# PROC091F_BT_DISPLAY.net
KiCad netlist of a schematic drawn in Altium Designer
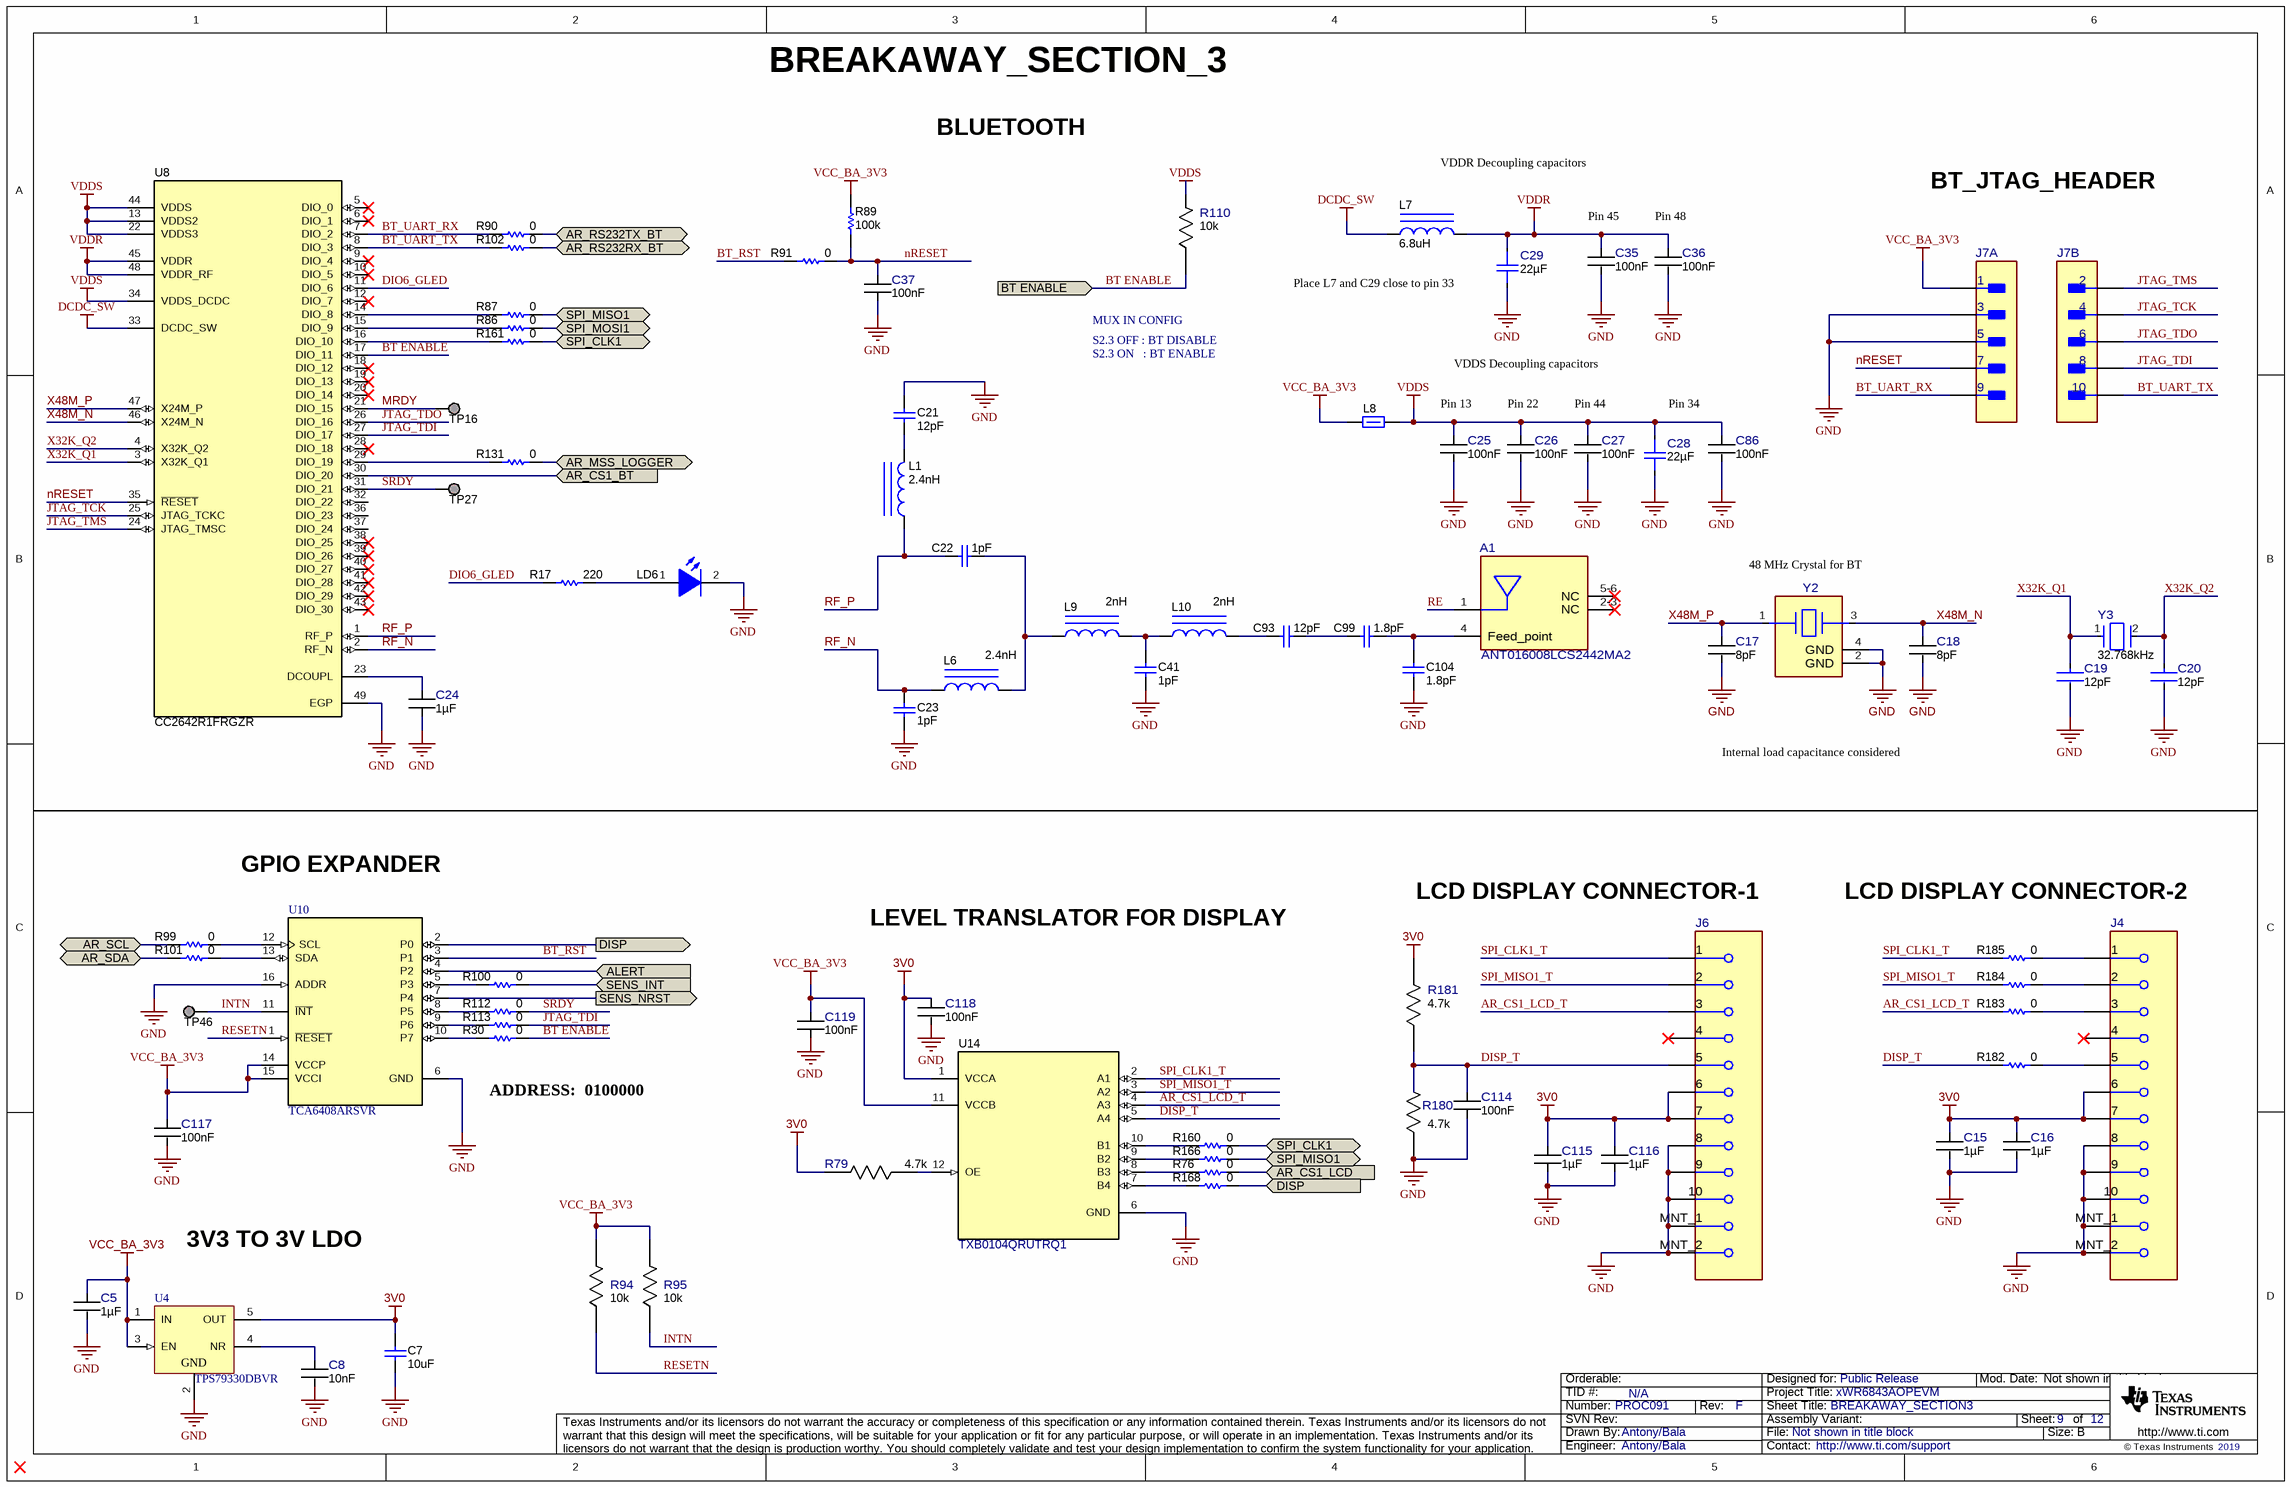
[diagram p0: PROC091F_BT_DISPLAY.SchDoc]

(export (version "E")
  (design (tool "Eeschema 10.0.6"))
  (components
    (comp (ref "A1")
      (value "ANT016008LCS2442MA2")
      (footprint "FP-ANT016008LCS2442MA2_SMT_ANT-0")
      (description "RF ANT 2.4GHZ CHIP SOLDER SMD")
      (fields (field (name "MANUFACTURER") "TDK Corporation"))
      (libsource (lib "Altium Vault - TI") (part "SYM-ANT016008LCS2442MA2"))
    )
    (comp (ref "C5")
      (value "CL03A105MO3NRNH")
      (footprint "FP-CL03A105MO3NRNH_0201-IPC_C")
      (description "1µF ±20% 16V Ceramic Capacitor X5R 0201")
      (fields (field (name "CAP_F") "1µF") (field (name "MANUFACTURER") "Samsung Electro-Mechanics"))
      (libsource (lib "Altium Vault - TI") (part "SYM-B32642B0223J"))
    )
    (comp (ref "C7")
      (value "10uF")
      (footprint "0402_070")
      (description "CAP, CERM, 10 uF, 10 V, +/- 20%, X5R, 0402")
      (fields
        (field (name "MANUFACTURER") "Samsung Electro-Mechanics")
        (field (name "PARTNUMBER") "CL05A106MP5NUNC")
      )
      (libsource (lib "Altium Vault - TI") (part "Capacitor"))
    )
    (comp (ref "C8")
      (value "CL03A103KA3NNNC")
      (footprint "FP-CL03A103KA3NNNC_0201-IPC_C")
      (description "CAP CER 10000PF 25V X5R 0201")
      (fields
        (field (name "CAP_F") "10nF")
        (field (name "MANUFACTURER") "Samsung Electro-Mechanics America, Inc")
      )
      (libsource (lib "Altium Vault - TI") (part "SYM-B32642B0223J"))
    )
    (comp (ref "C15")
      (value "CL03A105MO3NRNH")
      (footprint "FP-CL03A105MO3NRNH_0201-IPC_C")
      (description "1µF ±20% 16V Ceramic Capacitor X5R 0201")
      (fields (field (name "CAP_F") "1µF") (field (name "MANUFACTURER") "Samsung Electro-Mechanics"))
      (libsource (lib "Altium Vault - TI") (part "SYM-B32642B0223J"))
    )
    (comp (ref "C16")
      (value "CL03A105MO3NRNH")
      (footprint "FP-CL03A105MO3NRNH_0201-IPC_C")
      (description "1µF ±20% 16V Ceramic Capacitor X5R 0201")
      (fields (field (name "CAP_F") "1µF") (field (name "MANUFACTURER") "Samsung Electro-Mechanics"))
      (libsource (lib "Altium Vault - TI") (part "SYM-B32642B0223J"))
    )
    (comp (ref "C17")
      (value "GRM0335C1H8R0BA01D")
      (footprint "FP-GRM0335C1H8R0BA01D_0201 (0603 metric)-IPC_C")
      (description "Cap Ceramic 8pF 50V C0G 0.1pF SMD 0201 125°C Paper T/R")
      (fields (field (name "CAP_F") "8pF") (field (name "MANUFACTURER") "Murata"))
      (libsource (lib "Altium Vault - TI") (part "SYM-B32642B0223J"))
    )
    (comp (ref "C18")
      (value "GRM0335C1H8R0BA01D")
      (footprint "FP-GRM0335C1H8R0BA01D_0201 (0603 metric)-IPC_C")
      (description "Cap Ceramic 8pF 50V C0G 0.1pF SMD 0201 125°C Paper T/R")
      (fields (field (name "CAP_F") "8pF") (field (name "MANUFACTURER") "Murata"))
      (libsource (lib "Altium Vault - TI") (part "SYM-B32642B0223J"))
    )
    (comp (ref "C19")
      (value "250R05L120JV4T")
      (footprint "FP-250R05L120JV4T_0201-IPC_C")
      (description "CAP CER 12PF 25V C0G/NP0 0201")
      (fields (field (name "CAP_F") "12pF") (field (name "MANUFACTURER") "Johanson Technology Inc."))
      (libsource (lib "Altium Vault - TI") (part "SYM-CL31B335KAHVPNE"))
    )
    (comp (ref "C20")
      (value "250R05L120JV4T")
      (footprint "FP-250R05L120JV4T_0201-IPC_C")
      (description "CAP CER 12PF 25V C0G/NP0 0201")
      (fields (field (name "CAP_F") "12pF") (field (name "MANUFACTURER") "Johanson Technology Inc."))
      (libsource (lib "Altium Vault - TI") (part "SYM-CL31B335KAHVPNE"))
    )
    (comp (ref "C21")
      (value "CL05C120JB5NNNC")
      (footprint "0402L")
      (description "CAP, CERM, 12 pF, 50 V, +/- 5%, C0G/NP0, 0402")
      (fields
        (field (name "MANUFACTURER") "Samsung Electro-Mechanics")
        (field (name "VALUEDISPLAYED") "12pF")
        (field (name "PUBLISHER") "Texas Instruments")
      )
      (libsource (lib "Altium Vault - TI") (part "Capacitor"))
    )
    (comp (ref "C22")
      (value "GCM1555C1H1R0CA16D")
      (footprint "0402L")
      (description "CAP, CERM, 1 pF, 50 V,+/- 25%, C0G/NP0, AEC-Q200 Grade 1, 0402")
      (fields (field (name "VALUEDISPLAYED") "1pF") (field (name "MANUFACTURER") "MuRata"))
      (libsource (lib "Altium Vault - TI") (part "Capacitor"))
    )
    (comp (ref "C23")
      (value "GCM1555C1H1R0CA16D")
      (footprint "0402L")
      (description "CAP, CERM, 1 pF, 50 V,+/- 25%, C0G/NP0, AEC-Q200 Grade 1, 0402")
      (fields (field (name "VALUEDISPLAYED") "1pF") (field (name "MANUFACTURER") "MuRata"))
      (libsource (lib "Altium Vault - TI") (part "Capacitor"))
    )
    (comp (ref "C24")
      (value "CL03A105MO3NRNH")
      (footprint "FP-CL03A105MO3NRNH_0201-IPC_C")
      (description "1µF ±20% 16V Ceramic Capacitor X5R 0201")
      (fields (field (name "CAP_F") "1µF") (field (name "MANUFACTURER") "Samsung Electro-Mechanics"))
      (libsource (lib "Altium Vault - TI") (part "SYM-B32642B0223J"))
    )
    (comp (ref "C25")
      (value "GRM033R6YA104KE14D")
      (footprint "FP-GRM033R6YA104KE14D_0201 (0603 Metric)-IPC_C")
      (description "Cap Ceramic 0.1uF 35V X5R 10% Pad SMD 0201 85C T/R")
      (fields (field (name "CAP_F") "100nF") (field (name "MANUFACTURER") "Murata Electronics North America"))
      (libsource (lib "Altium Vault - TI") (part "SYM-B32642B0223J"))
    )
    (comp (ref "C26")
      (value "GRM033R6YA104KE14D")
      (footprint "FP-GRM033R6YA104KE14D_0201 (0603 Metric)-IPC_C")
      (description "Cap Ceramic 0.1uF 35V X5R 10% Pad SMD 0201 85C T/R")
      (fields (field (name "CAP_F") "100nF") (field (name "MANUFACTURER") "Murata Electronics North America"))
      (libsource (lib "Altium Vault - TI") (part "SYM-B32642B0223J"))
    )
    (comp (ref "C27")
      (value "GRM033R6YA104KE14D")
      (footprint "FP-GRM033R6YA104KE14D_0201 (0603 Metric)-IPC_C")
      (description "Cap Ceramic 0.1uF 35V X5R 10% Pad SMD 0201 85C T/R")
      (fields (field (name "CAP_F") "100nF") (field (name "MANUFACTURER") "Murata Electronics North America"))
      (libsource (lib "Altium Vault - TI") (part "SYM-B32642B0223J"))
    )
    (comp (ref "C28")
      (value "CL05A226MQ5N6J8")
      (footprint "FP-CL05A226MQ5N6J8_0402-IPC_C")
      (description "CAP CER 22UF 6.3V X5R 0402")
      (fields (field (name "CAP_F") "22µF") (field (name "MANUFACTURER") "Samsung Electro-Mechanics"))
      (libsource (lib "Altium Vault - TI") (part "SYM-C0603C220K5RACAUTO"))
    )
    (comp (ref "C29")
      (value "CL05A226MQ5N6J8")
      (footprint "FP-CL05A226MQ5N6J8_0402-IPC_C")
      (description "CAP CER 22UF 6.3V X5R 0402")
      (fields (field (name "CAP_F") "22µF") (field (name "MANUFACTURER") "Samsung Electro-Mechanics"))
      (libsource (lib "Altium Vault - TI") (part "SYM-C0603C220K5RACAUTO"))
    )
    (comp (ref "C35")
      (value "GRM033R6YA104KE14D")
      (footprint "FP-GRM033R6YA104KE14D_0201 (0603 Metric)-IPC_C")
      (description "Cap Ceramic 0.1uF 35V X5R 10% Pad SMD 0201 85C T/R")
      (fields (field (name "CAP_F") "100nF") (field (name "MANUFACTURER") "Murata Electronics North America"))
      (libsource (lib "Altium Vault - TI") (part "SYM-B32642B0223J"))
    )
    (comp (ref "C36")
      (value "GRM033R6YA104KE14D")
      (footprint "FP-GRM033R6YA104KE14D_0201 (0603 Metric)-IPC_C")
      (description "Cap Ceramic 0.1uF 35V X5R 10% Pad SMD 0201 85C T/R")
      (fields (field (name "CAP_F") "100nF") (field (name "MANUFACTURER") "Murata Electronics North America"))
      (libsource (lib "Altium Vault - TI") (part "SYM-B32642B0223J"))
    )
    (comp (ref "C37")
      (value "GRM033R6YA104KE14D")
      (footprint "FP-GRM033R6YA104KE14D_0201 (0603 Metric)-IPC_C")
      (description "Cap Ceramic 0.1uF 35V X5R 10% Pad SMD 0201 85C T/R")
      (fields (field (name "CAP_F") "100nF") (field (name "MANUFACTURER") "Murata Electronics North America"))
      (libsource (lib "Altium Vault - TI") (part "SYM-B32642B0223J"))
    )
    (comp (ref "C41")
      (value "GCM1555C1H1R0CA16D")
      (footprint "0402L")
      (description "CAP, CERM, 1 pF, 50 V,+/- 25%, C0G/NP0, AEC-Q200 Grade 1, 0402")
      (fields (field (name "VALUEDISPLAYED") "1pF") (field (name "MANUFACTURER") "MuRata"))
      (libsource (lib "Altium Vault - TI") (part "Capacitor"))
    )
    (comp (ref "C86")
      (value "GRM033R6YA104KE14D")
      (footprint "FP-GRM033R6YA104KE14D_0201 (0603 Metric)-IPC_C")
      (description "Cap Ceramic 0.1uF 35V X5R 10% Pad SMD 0201 85C T/R")
      (fields (field (name "CAP_F") "100nF") (field (name "MANUFACTURER") "Murata Electronics North America"))
      (libsource (lib "Altium Vault - TI") (part "SYM-B32642B0223J"))
    )
    (comp (ref "C93")
      (value "CL05C120JB5NNNC")
      (footprint "0402L")
      (description "CAP, CERM, 12 pF, 50 V, +/- 5%, C0G/NP0, 0402")
      (fields
        (field (name "MANUFACTURER") "Samsung Electro-Mechanics")
        (field (name "VALUEDISPLAYED") "12pF")
        (field (name "PUBLISHER") "Texas Instruments")
      )
      (libsource (lib "Altium Vault - TI") (part "Capacitor"))
    )
    (comp (ref "C99")
      (value "GJM1555C1H1R8BB01D")
      (footprint "0402L")
      (description "CAP, CERM, 1.8 pF, 50 V,+/- 6%, C0G/NP0, 0402")
      (fields (field (name "VALUEDISPLAYED") "1.8pF") (field (name "MANUFACTURER") "MuRata"))
      (libsource (lib "Altium Vault - TI") (part "Capacitor"))
    )
    (comp (ref "C104")
      (value "GJM1555C1H1R8BB01D")
      (footprint "0402L")
      (description "CAP, CERM, 1.8 pF, 50 V,+/- 6%, C0G/NP0, 0402")
      (fields (field (name "VALUEDISPLAYED") "1.8pF") (field (name "MANUFACTURER") "MuRata"))
      (libsource (lib "Altium Vault - TI") (part "Capacitor"))
    )
    (comp (ref "C114")
      (value "GRM033R6YA104KE14D")
      (footprint "FP-GRM033R6YA104KE14D_0201 (0603 Metric)-IPC_C")
      (description "Cap Ceramic 0.1uF 35V X5R 10% Pad SMD 0201 85C T/R")
      (fields (field (name "CAP_F") "100nF") (field (name "MANUFACTURER") "Murata Electronics North America"))
      (libsource (lib "Altium Vault - TI") (part "SYM-B32642B0223J"))
    )
    (comp (ref "C115")
      (value "CL03A105MO3NRNH")
      (footprint "FP-CL03A105MO3NRNH_0201-IPC_C")
      (description "1µF ±20% 16V Ceramic Capacitor X5R 0201")
      (fields (field (name "CAP_F") "1µF") (field (name "MANUFACTURER") "Samsung Electro-Mechanics"))
      (libsource (lib "Altium Vault - TI") (part "SYM-B32642B0223J"))
    )
    (comp (ref "C116")
      (value "CL03A105MO3NRNH")
      (footprint "FP-CL03A105MO3NRNH_0201-IPC_C")
      (description "1µF ±20% 16V Ceramic Capacitor X5R 0201")
      (fields (field (name "CAP_F") "1µF") (field (name "MANUFACTURER") "Samsung Electro-Mechanics"))
      (libsource (lib "Altium Vault - TI") (part "SYM-B32642B0223J"))
    )
    (comp (ref "C117")
      (value "GRM033R6YA104KE14D")
      (footprint "FP-GRM033R6YA104KE14D_0201 (0603 Metric)-IPC_C")
      (description "Cap Ceramic 0.1uF 35V X5R 10% Pad SMD 0201 85C T/R")
      (fields (field (name "CAP_F") "100nF") (field (name "MANUFACTURER") "Murata Electronics North America"))
      (libsource (lib "Altium Vault - TI") (part "SYM-B32642B0223J"))
    )
    (comp (ref "C118")
      (value "GRM033R6YA104KE14D")
      (footprint "FP-GRM033R6YA104KE14D_0201 (0603 Metric)-IPC_C")
      (description "Cap Ceramic 0.1uF 35V X5R 10% Pad SMD 0201 85C T/R")
      (fields (field (name "CAP_F") "100nF") (field (name "MANUFACTURER") "Murata Electronics North America"))
      (libsource (lib "Altium Vault - TI") (part "SYM-B32642B0223J"))
    )
    (comp (ref "C119")
      (value "GRM033R6YA104KE14D")
      (footprint "FP-GRM033R6YA104KE14D_0201 (0603 Metric)-IPC_C")
      (description "Cap Ceramic 0.1uF 35V X5R 10% Pad SMD 0201 85C T/R")
      (fields (field (name "CAP_F") "100nF") (field (name "MANUFACTURER") "Murata Electronics North America"))
      (libsource (lib "Altium Vault - TI") (part "SYM-B32642B0223J"))
    )
    (comp (ref "J4")
      (value "51441-1093")
      (footprint "FP-51441-1093_CONN_SMD_FFC-0")
      (fields (field (name "MANUFACTURER") "Molex"))
      (libsource (lib "Altium Vault - TI") (part "SYM-51441-1093"))
    )
    (comp (ref "J6")
      (value "51441-1093")
      (footprint "FP-51441-1093_CONN_SMD_FFC-0")
      (fields (field (name "MANUFACTURER") "Molex"))
      (libsource (lib "Altium Vault - TI") (part "SYM-51441-1093"))
    )
    (comp (ref "J7")
      (value "GRPB052MWCN-RC")
      (footprint "FP-GRPB052MWCN-RC_HDR10-MFG")
      (description "CONN HEADER R/A 10POS 1.27MM")
      (fields (field (name "MANUFACTURER") "Sullins"))
      (libsource (lib "Altium Vault - TI") (part "SYM-GRPB052MWCN-RC"))
    )
    (comp (ref "L1")
      (value "LQG15HS2N4S02D")
      (footprint "IND_LQG15H")
      (description "Inductor, Multilayer, Air Core, 2.4 nH, 0.3 A, 0.15 ohm, SMD")
      (fields
        (field (name "MANUFACTURER") "MuRata")
        (field (name "VALUEDISPLAYED") "2.4nH")
        (field (name "PUBLISHER") "Texas Instruments")
      )
      (libsource (lib "Altium Vault - TI") (part "Inductor_Iron"))
    )
    (comp (ref "L6")
      (value "LQG15HS2N4S02D")
      (footprint "IND_LQG15H")
      (description "Inductor, Multilayer, Air Core, 2.4 nH, 0.3 A, 0.15 ohm, SMD")
      (fields
        (field (name "MANUFACTURER") "MuRata")
        (field (name "VALUEDISPLAYED") "2.4nH")
        (field (name "PUBLISHER") "Texas Instruments")
      )
      (libsource (lib "Altium Vault - TI") (part "Inductor_Iron"))
    )
    (comp (ref "L7")
      (value "MLZ2012N6R8LT000")
      (footprint "0805_HV")
      (description "Inductor, Multilayer, Ferrite, 6.8 uH, 0.11 A, 0.25 ohm, SMD")
      (fields
        (field (name "MANUFACTURER") "TDK")
        (field (name "VALUEDISPLAYED") "6.8uH")
        (field (name "PUBLISHER") "Texas Instruments")
      )
      (libsource (lib "Altium Vault - TI") (part "Inductor_Iron"))
    )
    (comp (ref "L8")
      (value "BLM18HE152SN1D")
      (footprint "0603L")
      (description "Ferrite Bead, 1500 ohm @ 100 MHz, 0.5 A, 0603")
      (fields (field (name "MANUFACTURER") "MuRata") (field (name "PUBLISHER") "Texas Instruments"))
      (libsource (lib "Altium Vault - TI") (part "Ferrite_Bead"))
    )
    (comp (ref "L9")
      (value "LQG15HS2N0S02D")
      (footprint "IND_LQG15H")
      (description "Inductor, Multilayer, Air Core, 2 nH, 0.3 A, 0.1 ohm, SMD")
      (fields
        (field (name "MANUFACTURER") "MuRata")
        (field (name "VALUEDISPLAYED") "2nH")
        (field (name "PUBLISHER") "Texas Instruments")
      )
      (libsource (lib "Altium Vault - TI") (part "Inductor_Iron"))
    )
    (comp (ref "L10")
      (value "LQG15HS2N0S02D")
      (footprint "IND_LQG15H")
      (description "Inductor, Multilayer, Air Core, 2 nH, 0.3 A, 0.1 ohm, SMD")
      (fields
        (field (name "MANUFACTURER") "MuRata")
        (field (name "VALUEDISPLAYED") "2nH")
        (field (name "PUBLISHER") "Texas Instruments")
      )
      (libsource (lib "Altium Vault - TI") (part "Inductor_Iron"))
    )
    (comp (ref "LD6")
      (value "APHHS1005CGCK")
      (footprint "APHHS1005_Green")
      (description "LED, Green, SMD")
      (fields (field (name "MANUFACTURER") "Kingbright"))
      (libsource (lib "Altium Vault - TI") (part "LED"))
    )
    (comp (ref "R17")
      (value "220")
      (footprint "0201L")
      (description "RES, 220, 5%, 0.05 W, 0201")
      (fields
        (field (name "MANUFACTURER") "Yageo America")
        (field (name "PARTNUMBER") "RC0201JR-07220RL")
        (field (name "PUBLISHER") "Texas Instruments")
      )
      (libsource (lib "Altium Vault - TI") (part "Resistor"))
    )
    (comp (ref "R30")
      (value "RC0201JR-070RL")
      (footprint "FP-RC0201JR-070RL_0201 (0603 Metric)-MFG")
      (description "RES SMD 0 OHM JUMPER 1/20W 0201")
      (fields (field (name "MANUFACTURER") "Yageo") (field (name "RES_OHM") "0"))
      (libsource (lib "Altium Vault - TI") (part "SYM-WSR3R1500F"))
    )
    (comp (ref "R76")
      (value "RC0201JR-070RL")
      (footprint "FP-RC0201JR-070RL_0201 (0603 Metric)-IPC_C")
      (description "RES SMD 0 OHM JUMPER 1/20W 0201")
      (fields (field (name "MANUFACTURER") "Yageo") (field (name "RES_OHM") "0"))
      (libsource (lib "Altium Vault - TI") (part "SYM-WSR3R1500F"))
    )
    (comp (ref "R79")
      (value "ERJ-1GNF4701C")
      (footprint "FP-ERJ-1GNF4701C_0201-IPC_C")
      (description "RESISTOR, 0201, 0.05W, 1%, 4K7")
      (fields (field (name "MANUFACTURER") "Panasonic Electronic Components") (field (name "RES_OHM") "4.7k"))
      (libsource (lib "Altium Vault - TI") (part "SYM-PMR18EZPJ000"))
    )
    (comp (ref "R86")
      (value "RC0201JR-070RL")
      (footprint "FP-RC0201JR-070RL_0201 (0603 Metric)-IPC_C")
      (description "RES SMD 0 OHM JUMPER 1/20W 0201")
      (fields (field (name "MANUFACTURER") "Yageo") (field (name "RES_OHM") "0"))
      (libsource (lib "Altium Vault - TI") (part "SYM-WSR3R1500F"))
    )
    (comp (ref "R87")
      (value "RC0201JR-070RL")
      (footprint "FP-RC0201JR-070RL_0201 (0603 Metric)-IPC_C")
      (description "RES SMD 0 OHM JUMPER 1/20W 0201")
      (fields (field (name "MANUFACTURER") "Yageo") (field (name "RES_OHM") "0"))
      (libsource (lib "Altium Vault - TI") (part "SYM-WSR3R1500F"))
    )
    (comp (ref "R89")
      (value "100k")
      (footprint "0201L")
      (description "RES, 100 k, 1%, 0.05 W, 0201")
      (fields (field (name "MANUFACTURER") "Vishay-Dale") (field (name "PARTNUMBER") "CRCW0201100KFKED"))
      (libsource (lib "Altium Vault - TI") (part "Resistor"))
    )
    (comp (ref "R90")
      (value "RC0201JR-070RL")
      (footprint "FP-RC0201JR-070RL_0201 (0603 Metric)-IPC_C")
      (description "RES SMD 0 OHM JUMPER 1/20W 0201")
      (fields (field (name "MANUFACTURER") "Yageo") (field (name "RES_OHM") "0"))
      (libsource (lib "Altium Vault - TI") (part "SYM-WSR3R1500F"))
    )
    (comp (ref "R91")
      (value "RC0201JR-070RL")
      (footprint "FP-RC0201JR-070RL_0201 (0603 Metric)-IPC_C")
      (description "RES SMD 0 OHM JUMPER 1/20W 0201")
      (fields (field (name "MANUFACTURER") "Yageo") (field (name "RES_OHM") "0"))
      (libsource (lib "Altium Vault - TI") (part "SYM-WSR3R1500F"))
    )
    (comp (ref "R94")
      (value "RR0306P-103-D")
      (footprint "FP-RR0306P-103-D_0201-IPC_C")
      (description "10 kOhms ±0.5% 0.05W, 1/20W Chip Resistor 0201 (0603 Metric)  Thin Film")
      (fields (field (name "MANUFACTURER") "Susumu") (field (name "RES_OHM") "10k"))
      (libsource (lib "Altium Vault - TI") (part "SYM-PMR18EZPJ000"))
    )
    (comp (ref "R95")
      (value "RR0306P-103-D")
      (footprint "FP-RR0306P-103-D_0201-IPC_C")
      (description "10 kOhms ±0.5% 0.05W, 1/20W Chip Resistor 0201 (0603 Metric)  Thin Film")
      (fields (field (name "MANUFACTURER") "Susumu") (field (name "RES_OHM") "10k"))
      (libsource (lib "Altium Vault - TI") (part "SYM-PMR18EZPJ000"))
    )
    (comp (ref "R99")
      (value "RC0201JR-070RL")
      (footprint "FP-RC0201JR-070RL_0201 (0603 Metric)-IPC_C")
      (description "RES SMD 0 OHM JUMPER 1/20W 0201")
      (fields (field (name "MANUFACTURER") "Yageo") (field (name "RES_OHM") "0"))
      (libsource (lib "Altium Vault - TI") (part "SYM-WSR3R1500F"))
    )
    (comp (ref "R100")
      (value "RC0201JR-070RL")
      (footprint "FP-RC0201JR-070RL_0201 (0603 Metric)-IPC_C")
      (description "RES SMD 0 OHM JUMPER 1/20W 0201")
      (fields (field (name "MANUFACTURER") "Yageo") (field (name "RES_OHM") "0"))
      (libsource (lib "Altium Vault - TI") (part "SYM-WSR3R1500F"))
    )
    (comp (ref "R101")
      (value "RC0201JR-070RL")
      (footprint "FP-RC0201JR-070RL_0201 (0603 Metric)-IPC_C")
      (description "RES SMD 0 OHM JUMPER 1/20W 0201")
      (fields (field (name "MANUFACTURER") "Yageo") (field (name "RES_OHM") "0"))
      (libsource (lib "Altium Vault - TI") (part "SYM-WSR3R1500F"))
    )
    (comp (ref "R102")
      (value "RC0201JR-070RL")
      (footprint "FP-RC0201JR-070RL_0201 (0603 Metric)-IPC_C")
      (description "RES SMD 0 OHM JUMPER 1/20W 0201")
      (fields (field (name "MANUFACTURER") "Yageo") (field (name "RES_OHM") "0"))
      (libsource (lib "Altium Vault - TI") (part "SYM-WSR3R1500F"))
    )
    (comp (ref "R110")
      (value "RR0306P-103-D")
      (footprint "FP-RR0306P-103-D_0201-IPC_C")
      (description "10 kOhms ±0.5% 0.05W, 1/20W Chip Resistor 0201 (0603 Metric)  Thin Film")
      (fields (field (name "MANUFACTURER") "Susumu") (field (name "RES_OHM") "10k"))
      (libsource (lib "Altium Vault - TI") (part "SYM-PMR18EZPJ000"))
    )
    (comp (ref "R112")
      (value "RC0201JR-070RL")
      (footprint "FP-RC0201JR-070RL_0201 (0603 Metric)-IPC_C")
      (description "RES SMD 0 OHM JUMPER 1/20W 0201")
      (fields (field (name "MANUFACTURER") "Yageo") (field (name "RES_OHM") "0"))
      (libsource (lib "Altium Vault - TI") (part "SYM-WSR3R1500F"))
    )
    (comp (ref "R113")
      (value "RC0201JR-070RL")
      (footprint "FP-RC0201JR-070RL_0201 (0603 Metric)-IPC_C")
      (description "RES SMD 0 OHM JUMPER 1/20W 0201")
      (fields (field (name "MANUFACTURER") "Yageo") (field (name "RES_OHM") "0"))
      (libsource (lib "Altium Vault - TI") (part "SYM-WSR3R1500F"))
    )
    (comp (ref "R131")
      (value "RC0201JR-070RL")
      (footprint "FP-RC0201JR-070RL_0201 (0603 Metric)-IPC_C")
      (description "RES SMD 0 OHM JUMPER 1/20W 0201")
      (fields (field (name "MANUFACTURER") "Yageo") (field (name "RES_OHM") "0"))
      (libsource (lib "Altium Vault - TI") (part "SYM-WSR3R1500F"))
    )
    (comp (ref "R160")
      (value "RC0201JR-070RL")
      (footprint "FP-RC0201JR-070RL_0201 (0603 Metric)-IPC_C")
      (description "RES SMD 0 OHM JUMPER 1/20W 0201")
      (fields (field (name "MANUFACTURER") "Yageo") (field (name "RES_OHM") "0"))
      (libsource (lib "Altium Vault - TI") (part "SYM-WSR3R1500F"))
    )
    (comp (ref "R161")
      (value "RC0201JR-070RL")
      (footprint "FP-RC0201JR-070RL_0201 (0603 Metric)-IPC_C")
      (description "RES SMD 0 OHM JUMPER 1/20W 0201")
      (fields (field (name "MANUFACTURER") "Yageo") (field (name "RES_OHM") "0"))
      (libsource (lib "Altium Vault - TI") (part "SYM-WSR3R1500F"))
    )
    (comp (ref "R166")
      (value "RC0201JR-070RL")
      (footprint "FP-RC0201JR-070RL_0201 (0603 Metric)-IPC_C")
      (description "RES SMD 0 OHM JUMPER 1/20W 0201")
      (fields (field (name "MANUFACTURER") "Yageo") (field (name "RES_OHM") "0"))
      (libsource (lib "Altium Vault - TI") (part "SYM-WSR3R1500F"))
    )
    (comp (ref "R168")
      (value "RC0201JR-070RL")
      (footprint "FP-RC0201JR-070RL_0201 (0603 Metric)-IPC_C")
      (description "RES SMD 0 OHM JUMPER 1/20W 0201")
      (fields (field (name "MANUFACTURER") "Yageo") (field (name "RES_OHM") "0"))
      (libsource (lib "Altium Vault - TI") (part "SYM-WSR3R1500F"))
    )
    (comp (ref "R180")
      (value "ERJ-1GNF4701C")
      (footprint "FP-ERJ-1GNF4701C_0201-IPC_C")
      (description "RESISTOR, 0201, 0.05W, 1%, 4K7")
      (fields (field (name "MANUFACTURER") "Panasonic Electronic Components") (field (name "RES_OHM") "4.7k"))
      (libsource (lib "Altium Vault - TI") (part "SYM-PMR18EZPJ000"))
    )
    (comp (ref "R181")
      (value "ERJ-1GNF4701C")
      (footprint "FP-ERJ-1GNF4701C_0201-IPC_C")
      (description "RESISTOR, 0201, 0.05W, 1%, 4K7")
      (fields (field (name "MANUFACTURER") "Panasonic Electronic Components") (field (name "RES_OHM") "4.7k"))
      (libsource (lib "Altium Vault - TI") (part "SYM-PMR18EZPJ000"))
    )
    (comp (ref "R182")
      (value "RC0201JR-070RL")
      (footprint "FP-RC0201JR-070RL_0201 (0603 Metric)-IPC_C")
      (description "RES SMD 0 OHM JUMPER 1/20W 0201")
      (fields (field (name "MANUFACTURER") "Yageo") (field (name "RES_OHM") "0"))
      (libsource (lib "Altium Vault - TI") (part "SYM-WSR3R1500F"))
    )
    (comp (ref "R183")
      (value "RC0201JR-070RL")
      (footprint "FP-RC0201JR-070RL_0201 (0603 Metric)-IPC_C")
      (description "RES SMD 0 OHM JUMPER 1/20W 0201")
      (fields (field (name "MANUFACTURER") "Yageo") (field (name "RES_OHM") "0"))
      (libsource (lib "Altium Vault - TI") (part "SYM-WSR3R1500F"))
    )
    (comp (ref "R184")
      (value "RC0201JR-070RL")
      (footprint "FP-RC0201JR-070RL_0201 (0603 Metric)-IPC_C")
      (description "RES SMD 0 OHM JUMPER 1/20W 0201")
      (fields (field (name "MANUFACTURER") "Yageo") (field (name "RES_OHM") "0"))
      (libsource (lib "Altium Vault - TI") (part "SYM-WSR3R1500F"))
    )
    (comp (ref "R185")
      (value "RC0201JR-070RL")
      (footprint "FP-RC0201JR-070RL_0201 (0603 Metric)-IPC_C")
      (description "RES SMD 0 OHM JUMPER 1/20W 0201")
      (fields (field (name "MANUFACTURER") "Yageo") (field (name "RES_OHM") "0"))
      (libsource (lib "Altium Vault - TI") (part "SYM-WSR3R1500F"))
    )
    (comp (ref "TP16")
      (value "TESTPOINT")
      (footprint "TP_25MIL-SMT")
      (description "TEST POINT.  No entry in BOM.")
      (libsource (lib "Altium Vault - TI") (part "TESTPOINT"))
    )
    (comp (ref "TP27")
      (value "TESTPOINT")
      (footprint "TP_25MIL-SMT")
      (description "TEST POINT.  No entry in BOM.")
      (libsource (lib "Altium Vault - TI") (part "TESTPOINT"))
    )
    (comp (ref "TP46")
      (value "TESTPOINT")
      (footprint "TP_25MIL-SMT")
      (description "TEST POINT.  No entry in BOM.")
      (libsource (lib "Altium Vault - TI") (part "TESTPOINT"))
    )
    (comp (ref "U4")
      (value "TPS79330DBVR")
      (footprint "DBV0005A_N")
      (fields (field (name "MANUFACTURER") "Texas Instruments"))
      (libsource (lib "Altium Vault - TI") (part "TI-TPS79NXX-YYSOT5"))
    )
    (comp (ref "U8")
      (value "CC2642R1FRGZR")
      (footprint "RGZ0048A")
      (description "SimpleLink(TM) Bluetooth(R) 5 low energy Wireless MCU, RGZ0048A (VQFN-48)")
      (fields
        (field (name "PARTNUMBER") "CC2642R1FRGZR")
        (field (name "MANUFACTURER") "Texas Instruments")
        (field (name "ALTERNATE PARTNUMBER") "CC2642R1FRGZT")
      )
      (libsource (lib "Altium Vault - TI") (part "CC26xx_RGZ"))
    )
    (comp (ref "U10")
      (value "TCA6408ARSVR")
      (footprint "RSV0016A")
      (fields (field (name "MANUFACTURER") "Texas Instruments"))
      (libsource (lib "Altium Vault - TI") (part "TI-TCA6408A-UQFN_RSV-16"))
    )
    (comp (ref "U14")
      (value "TXB0104QRUTRQ1")
      (footprint "RUT0012A")
      (fields (field (name "MANUFACTURER") "Texas Instruments"))
      (libsource (lib "Altium Vault - TI") (part "TXB0104QRUTRQ1"))
    )
    (comp (ref "Y2")
      (value "CX2016DB48000C0WPLA2")
      (footprint "FP-CX2016DB48000C0WPLA2_SMD4-MFG")
      (description "48MHz ±20ppm Crystal 7pF 50 Ohms 4-SMD, No Lead")
      (fields (field (name "MANUFACTURER") "Kyocera"))
      (libsource (lib "Altium Vault - TI") (part "SYM-CX2016DB48000C0WPLA2"))
    )
    (comp (ref "Y3")
      (value "ABS05W-32.768KHZ-D-2-T")
      (footprint "FP-ABS05W-32.768KHZ-D-2-T_XTAL_SMT_1MM6_1MM0-MFG")
      (description "CRYSTAL 32.768KHZ 4PF SMD")
      (fields (field (name "FREQUENCY_FIXED") "32.768kHz") (field (name "MANUFACTURER") "Abracon LLC"))
      (libsource (lib "Altium Vault - TI") (part "SYM-ABS05W-32.768KHZ-D-2-T"))
    )
  )
  (nets
    (net (code "1") (name "/ALERT") (class "Default")
      (node (ref "U10") (pin "4") (pinfunction "P2_4") (pintype "bidirectional"))
    )
    (net (code "2") (name "/AR_CS1_BT") (class "Default")
      (node (ref "U8") (pin "30") (pinfunction "DIO_20_30") (pintype "bidirectional"))
    )
    (net (code "3") (name "/AR_CS1_LCD") (class "Default")
      (node (ref "R76") (pin "2") (pinfunction "2_2") (pintype "passive"))
    )
    (net (code "4") (name "/AR_CS1_LCD_T") (class "Default")
      (node (ref "J6") (pin "3") (pinfunction "3_3") (pintype "passive"))
      (node (ref "R183") (pin "1") (pinfunction "1_1") (pintype "passive"))
      (node (ref "U14") (pin "4") (pinfunction "A3_4") (pintype "bidirectional"))
    )
    (net (code "5") (name "/AR_MSS_LOGGER") (class "Default")
      (node (ref "R131") (pin "1") (pinfunction "1_1") (pintype "passive"))
    )
    (net (code "6") (name "/AR_RS232RX_BT") (class "Default")
      (node (ref "R102") (pin "1") (pinfunction "1_1") (pintype "passive"))
    )
    (net (code "7") (name "/AR_RS232TX_BT") (class "Default")
      (node (ref "R90") (pin "1") (pinfunction "1_1") (pintype "passive"))
    )
    (net (code "8") (name "/AR_SCL") (class "Default")
      (node (ref "R99") (pin "2") (pinfunction "2_2") (pintype "passive"))
    )
    (net (code "9") (name "/AR_SDA") (class "Default")
      (node (ref "R101") (pin "2") (pinfunction "2_2") (pintype "passive"))
    )
    (net (code "10") (name "/BT ENABLE") (class "Default")
      (node (ref "R110") (pin "1") (pinfunction "1_1") (pintype "passive"))
      (node (ref "R30") (pin "1") (pinfunction "1_1") (pintype "passive"))
      (node (ref "U8") (pin "17") (pinfunction "DIO_11_17") (pintype "bidirectional"))
    )
    (net (code "11") (name "/BT_RST") (class "Default")
      (node (ref "R91") (pin "2") (pinfunction "2_2") (pintype "passive"))
      (node (ref "U10") (pin "3") (pinfunction "P1_3") (pintype "bidirectional"))
    )
    (net (code "12") (name "/BT_UART_RX") (class "Default")
      (node (ref "J7") (pin "9") (pinfunction "9_9") (pintype "passive"))
      (node (ref "R90") (pin "2") (pinfunction "2_2") (pintype "passive"))
      (node (ref "U8") (pin "7") (pinfunction "DIO_2_7") (pintype "bidirectional"))
    )
    (net (code "13") (name "/BT_UART_TX") (class "Default")
      (node (ref "J7") (pin "10") (pinfunction "10_10") (pintype "passive"))
      (node (ref "R102") (pin "2") (pinfunction "2_2") (pintype "passive"))
      (node (ref "U8") (pin "8") (pinfunction "DIO_3_8") (pintype "bidirectional"))
    )
    (net (code "14") (name "/DIO6_GLED") (class "Default")
      (node (ref "R17") (pin "1") (pinfunction "1_1") (pintype "passive"))
      (node (ref "U8") (pin "11") (pinfunction "DIO_6_11") (pintype "bidirectional"))
    )
    (net (code "15") (name "/DISP") (class "Default")
      (node (ref "R168") (pin "2") (pinfunction "2_2") (pintype "passive"))
      (node (ref "U10") (pin "2") (pinfunction "P0_2") (pintype "bidirectional"))
    )
    (net (code "16") (name "/DISP_T") (class "Default")
      (node (ref "C114") (pin "2") (pinfunction "2_2") (pintype "passive"))
      (node (ref "J6") (pin "5") (pinfunction "5_5") (pintype "passive"))
      (node (ref "R180") (pin "2") (pinfunction "2_2") (pintype "passive"))
      (node (ref "R181") (pin "1") (pinfunction "1_1") (pintype "passive"))
      (node (ref "R182") (pin "1") (pinfunction "1_1") (pintype "passive"))
      (node (ref "U14") (pin "5") (pinfunction "A4_5") (pintype "bidirectional"))
    )
    (net (code "17") (name "/INTN") (class "Default")
      (node (ref "R95") (pin "1") (pinfunction "1_1") (pintype "passive"))
      (node (ref "TP46") (pin "1") (pintype "passive"))
      (node (ref "U10") (pin "11") (pinfunction "~{INT}_11") (pintype "open_collector"))
    )
    (net (code "18") (name "/JTAG_TCK") (class "Default")
      (node (ref "J7") (pin "4") (pinfunction "4_4") (pintype "passive"))
      (node (ref "U8") (pin "25") (pinfunction "JTAG_TCKC_25") (pintype "bidirectional"))
    )
    (net (code "19") (name "/JTAG_TDI") (class "Default")
      (node (ref "J7") (pin "8") (pinfunction "8_8") (pintype "passive"))
      (node (ref "R113") (pin "1") (pinfunction "1_1") (pintype "passive"))
      (node (ref "U8") (pin "27") (pinfunction "DIO_17_27") (pintype "bidirectional"))
    )
    (net (code "20") (name "/JTAG_TDO") (class "Default")
      (node (ref "J7") (pin "6") (pinfunction "6_6") (pintype "passive"))
      (node (ref "U8") (pin "26") (pinfunction "DIO_16_26") (pintype "bidirectional"))
    )
    (net (code "21") (name "/JTAG_TMS") (class "Default")
      (node (ref "J7") (pin "2") (pinfunction "2_2") (pintype "passive"))
      (node (ref "U8") (pin "24") (pinfunction "JTAG_TMSC_24") (pintype "bidirectional"))
    )
    (net (code "22") (name "/MRDY") (class "Default")
      (node (ref "TP16") (pin "1") (pintype "passive"))
      (node (ref "U8") (pin "21") (pinfunction "DIO_15_21") (pintype "bidirectional"))
    )
    (net (code "23") (name "/RE") (class "Default")
      (node (ref "A1") (pin "1") (pinfunction "Radiator_electrode_1") (pintype "passive"))
    )
    (net (code "24") (name "/RESETN") (class "Default")
      (node (ref "R94") (pin "1") (pinfunction "1_1") (pintype "passive"))
      (node (ref "U10") (pin "1") (pinfunction "~{RESET}_1") (pintype "input"))
    )
    (net (code "25") (name "/RF_N") (class "Default")
      (node (ref "C23") (pin "1") (pinfunction "1_1") (pintype "passive"))
      (node (ref "L6") (pin "1") (pinfunction "1_1") (pintype "passive"))
      (node (ref "U8") (pin "2") (pinfunction "RF_N_2") (pintype "bidirectional"))
    )
    (net (code "26") (name "/RF_P") (class "Default")
      (node (ref "C22") (pin "2") (pinfunction "2_2") (pintype "passive"))
      (node (ref "L1") (pin "1") (pinfunction "1_1") (pintype "passive"))
      (node (ref "U8") (pin "1") (pinfunction "RF_P_1") (pintype "bidirectional"))
    )
    (net (code "27") (name "/SENS_INT") (class "Default")
      (node (ref "R100") (pin "1") (pinfunction "1_1") (pintype "passive"))
    )
    (net (code "28") (name "/SENS_NRST") (class "Default")
      (node (ref "U10") (pin "7") (pinfunction "P4_7") (pintype "bidirectional"))
    )
    (net (code "29") (name "/SPI_CLK1") (class "Default")
      (node (ref "R160") (pin "2") (pinfunction "2_2") (pintype "passive"))
      (node (ref "R161") (pin "1") (pinfunction "1_1") (pintype "passive"))
    )
    (net (code "30") (name "/SPI_CLK1_T") (class "Default")
      (node (ref "J6") (pin "1") (pinfunction "1_1") (pintype "passive"))
      (node (ref "R185") (pin "1") (pinfunction "1_1") (pintype "passive"))
      (node (ref "U14") (pin "2") (pinfunction "A1_2") (pintype "bidirectional"))
    )
    (net (code "31") (name "/SPI_MISO1") (class "Default")
      (node (ref "R166") (pin "2") (pinfunction "2_2") (pintype "passive"))
      (node (ref "R87") (pin "1") (pinfunction "1_1") (pintype "passive"))
    )
    (net (code "32") (name "/SPI_MISO1_T") (class "Default")
      (node (ref "J6") (pin "2") (pinfunction "2_2") (pintype "passive"))
      (node (ref "R184") (pin "1") (pinfunction "1_1") (pintype "passive"))
      (node (ref "U14") (pin "3") (pinfunction "A2_3") (pintype "bidirectional"))
    )
    (net (code "33") (name "/SPI_MOSI1") (class "Default")
      (node (ref "R86") (pin "1") (pinfunction "1_1") (pintype "passive"))
    )
    (net (code "34") (name "/SRDY") (class "Default")
      (node (ref "R112") (pin "1") (pinfunction "1_1") (pintype "passive"))
      (node (ref "TP27") (pin "1") (pintype "passive"))
      (node (ref "U8") (pin "31") (pinfunction "DIO_21_31") (pintype "bidirectional"))
    )
    (net (code "35") (name "/X32K_Q1") (class "Default")
      (node (ref "C19") (pin "1") (pinfunction "1_1") (pintype "passive"))
      (node (ref "U8") (pin "3") (pinfunction "X32K_Q1_3") (pintype "bidirectional"))
      (node (ref "Y3") (pin "1") (pinfunction "1_1") (pintype "passive"))
    )
    (net (code "36") (name "/X32K_Q2") (class "Default")
      (node (ref "C20") (pin "1") (pinfunction "1_1") (pintype "passive"))
      (node (ref "U8") (pin "4") (pinfunction "X32K_Q2_4") (pintype "bidirectional"))
      (node (ref "Y3") (pin "2") (pinfunction "2_2") (pintype "passive"))
    )
    (net (code "37") (name "/X48M_N") (class "Default")
      (node (ref "C18") (pin "1") (pinfunction "1_1") (pintype "passive"))
      (node (ref "U8") (pin "46") (pinfunction "X24M_N_46") (pintype "bidirectional"))
      (node (ref "Y2") (pin "3") (pinfunction "2_HOT_3") (pintype "passive"))
    )
    (net (code "38") (name "/X48M_P") (class "Default")
      (node (ref "C17") (pin "1") (pinfunction "1_1") (pintype "passive"))
      (node (ref "U8") (pin "47") (pinfunction "X24M_P_47") (pintype "bidirectional"))
      (node (ref "Y2") (pin "1") (pinfunction "1_HOT_1") (pintype "passive"))
    )
    (net (code "39") (name "/nRESET") (class "Default")
      (node (ref "C37") (pin "1") (pinfunction "1_1") (pintype "passive"))
      (node (ref "J7") (pin "7") (pinfunction "7_7") (pintype "passive"))
      (node (ref "R89") (pin "1") (pinfunction "1_1") (pintype "passive"))
      (node (ref "R91") (pin "1") (pinfunction "1_1") (pintype "passive"))
      (node (ref "U8") (pin "35") (pinfunction "RESET_35") (pintype "input"))
    )
    (net (code "40") (name "3V0") (class "Default")
      (node (ref "C115") (pin "1") (pinfunction "1_1") (pintype "passive"))
      (node (ref "C116") (pin "1") (pinfunction "1_1") (pintype "passive"))
      (node (ref "C118") (pin "1") (pinfunction "1_1") (pintype "passive"))
      (node (ref "C15") (pin "1") (pinfunction "1_1") (pintype "passive"))
      (node (ref "C16") (pin "1") (pinfunction "1_1") (pintype "passive"))
      (node (ref "C7") (pin "1") (pinfunction "1_1") (pintype "passive"))
      (node (ref "J4") (pin "6") (pinfunction "6_6") (pintype "passive"))
      (node (ref "J4") (pin "7") (pinfunction "7_7") (pintype "passive"))
      (node (ref "J6") (pin "6") (pinfunction "6_6") (pintype "passive"))
      (node (ref "J6") (pin "7") (pinfunction "7_7") (pintype "passive"))
      (node (ref "R181") (pin "2") (pinfunction "2_2") (pintype "passive"))
      (node (ref "R79") (pin "2") (pinfunction "2_2") (pintype "passive"))
      (node (ref "U14") (pin "1") (pinfunction "VCCA_1") (pintype "power_in"))
      (node (ref "U4") (pin "5") (pinfunction "OUT_5") (pintype "power_in"))
    )
    (net (code "41") (name "DCDC_SW") (class "Default")
      (node (ref "L7") (pin "1") (pinfunction "1_1") (pintype "passive"))
      (node (ref "U8") (pin "33") (pinfunction "DCDC_SW_33") (pintype "power_in"))
    )
    (net (code "42") (name "GND") (class "Default")
      (node (ref "C104") (pin "2") (pinfunction "2_2") (pintype "passive"))
      (node (ref "C114") (pin "1") (pinfunction "1_1") (pintype "passive"))
      (node (ref "C115") (pin "2") (pinfunction "2_2") (pintype "passive"))
      (node (ref "C116") (pin "2") (pinfunction "2_2") (pintype "passive"))
      (node (ref "C117") (pin "2") (pinfunction "2_2") (pintype "passive"))
      (node (ref "C118") (pin "2") (pinfunction "2_2") (pintype "passive"))
      (node (ref "C119") (pin "2") (pinfunction "2_2") (pintype "passive"))
      (node (ref "C15") (pin "2") (pinfunction "2_2") (pintype "passive"))
      (node (ref "C16") (pin "2") (pinfunction "2_2") (pintype "passive"))
      (node (ref "C17") (pin "2") (pinfunction "2_2") (pintype "passive"))
      (node (ref "C18") (pin "2") (pinfunction "2_2") (pintype "passive"))
      (node (ref "C19") (pin "2") (pinfunction "2_2") (pintype "passive"))
      (node (ref "C20") (pin "2") (pinfunction "2_2") (pintype "passive"))
      (node (ref "C21") (pin "1") (pinfunction "1_1") (pintype "passive"))
      (node (ref "C23") (pin "2") (pinfunction "2_2") (pintype "passive"))
      (node (ref "C24") (pin "2") (pinfunction "2_2") (pintype "passive"))
      (node (ref "C25") (pin "2") (pinfunction "2_2") (pintype "passive"))
      (node (ref "C26") (pin "2") (pinfunction "2_2") (pintype "passive"))
      (node (ref "C27") (pin "2") (pinfunction "2_2") (pintype "passive"))
      (node (ref "C28") (pin "2") (pinfunction "2_2") (pintype "passive"))
      (node (ref "C29") (pin "2") (pinfunction "2_2") (pintype "passive"))
      (node (ref "C35") (pin "2") (pinfunction "2_2") (pintype "passive"))
      (node (ref "C36") (pin "2") (pinfunction "2_2") (pintype "passive"))
      (node (ref "C37") (pin "2") (pinfunction "2_2") (pintype "passive"))
      (node (ref "C41") (pin "2") (pinfunction "2_2") (pintype "passive"))
      (node (ref "C5") (pin "2") (pinfunction "2_2") (pintype "passive"))
      (node (ref "C7") (pin "2") (pinfunction "2_2") (pintype "passive"))
      (node (ref "C8") (pin "2") (pinfunction "2_2") (pintype "passive"))
      (node (ref "C86") (pin "2") (pinfunction "2_2") (pintype "passive"))
      (node (ref "J4") (pin "10") (pinfunction "10_10") (pintype "passive"))
      (node (ref "J4") (pin "11") (pinfunction "MNT_1_11") (pintype "passive"))
      (node (ref "J4") (pin "12") (pinfunction "MNT_2_12") (pintype "passive"))
      (node (ref "J4") (pin "8") (pinfunction "8_8") (pintype "passive"))
      (node (ref "J4") (pin "9") (pinfunction "9_9") (pintype "passive"))
      (node (ref "J6") (pin "10") (pinfunction "10_10") (pintype "passive"))
      (node (ref "J6") (pin "11") (pinfunction "MNT_1_11") (pintype "passive"))
      (node (ref "J6") (pin "12") (pinfunction "MNT_2_12") (pintype "passive"))
      (node (ref "J6") (pin "8") (pinfunction "8_8") (pintype "passive"))
      (node (ref "J6") (pin "9") (pinfunction "9_9") (pintype "passive"))
      (node (ref "J7") (pin "3") (pinfunction "3_3") (pintype "passive"))
      (node (ref "J7") (pin "5") (pinfunction "5_5") (pintype "passive"))
      (node (ref "LD6") (pin "2") (pinfunction "K_2") (pintype "passive"))
      (node (ref "R180") (pin "1") (pinfunction "1_1") (pintype "passive"))
      (node (ref "U10") (pin "16") (pinfunction "ADDR_16") (pintype "input"))
      (node (ref "U10") (pin "6") (pinfunction "GND_6") (pintype "power_in"))
      (node (ref "U14") (pin "6") (pinfunction "GND_6") (pintype "power_in"))
      (node (ref "U4") (pin "2") (pinfunction "GND_2") (pintype "power_in"))
      (node (ref "U8") (pin "49") (pinfunction "EGP_49") (pintype "power_in"))
      (node (ref "Y2") (pin "2") (pinfunction "GND_2") (pintype "power_in"))
      (node (ref "Y2") (pin "4") (pinfunction "GND_4") (pintype "power_in"))
    )
    (net (code "43") (name "Net-(A1-Feed_point)") (class "Default")
      (node (ref "A1") (pin "4") (pinfunction "Feed_point_4") (pintype "passive"))
      (node (ref "C104") (pin "1") (pinfunction "1_1") (pintype "passive"))
      (node (ref "C99") (pin "1") (pinfunction "1_1") (pintype "passive"))
    )
    (net (code "44") (name "Net-(C21-Pad2)") (class "Default")
      (node (ref "C21") (pin "2") (pinfunction "2_2") (pintype "passive"))
      (node (ref "L1") (pin "2") (pinfunction "2_2") (pintype "passive"))
    )
    (net (code "45") (name "Net-(C22-Pad1)") (class "Default")
      (node (ref "C22") (pin "1") (pinfunction "1_1") (pintype "passive"))
      (node (ref "L6") (pin "2") (pinfunction "2_2") (pintype "passive"))
      (node (ref "L9") (pin "1") (pinfunction "1_1") (pintype "passive"))
    )
    (net (code "46") (name "Net-(C41-Pad1)") (class "Default")
      (node (ref "C41") (pin "1") (pinfunction "1_1") (pintype "passive"))
      (node (ref "L10") (pin "1") (pinfunction "1_1") (pintype "passive"))
      (node (ref "L9") (pin "2") (pinfunction "2_2") (pintype "passive"))
    )
    (net (code "47") (name "Net-(C93-Pad1)") (class "Default")
      (node (ref "C93") (pin "1") (pinfunction "1_1") (pintype "passive"))
      (node (ref "C99") (pin "2") (pinfunction "2_2") (pintype "passive"))
    )
    (net (code "48") (name "Net-(C93-Pad2)") (class "Default")
      (node (ref "C93") (pin "2") (pinfunction "2_2") (pintype "passive"))
      (node (ref "L10") (pin "2") (pinfunction "2_2") (pintype "passive"))
    )
    (net (code "49") (name "Net-(J4-Pad1)") (class "Default")
      (node (ref "J4") (pin "1") (pinfunction "1_1") (pintype "passive"))
      (node (ref "R185") (pin "2") (pinfunction "2_2") (pintype "passive"))
    )
    (net (code "50") (name "Net-(J4-Pad2)") (class "Default")
      (node (ref "J4") (pin "2") (pinfunction "2_2") (pintype "passive"))
      (node (ref "R184") (pin "2") (pinfunction "2_2") (pintype "passive"))
    )
    (net (code "51") (name "Net-(J4-Pad3)") (class "Default")
      (node (ref "J4") (pin "3") (pinfunction "3_3") (pintype "passive"))
      (node (ref "R183") (pin "2") (pinfunction "2_2") (pintype "passive"))
    )
    (net (code "52") (name "Net-(J4-Pad5)") (class "Default")
      (node (ref "J4") (pin "5") (pinfunction "5_5") (pintype "passive"))
      (node (ref "R182") (pin "2") (pinfunction "2_2") (pintype "passive"))
    )
    (net (code "53") (name "Net-(LD6-A)") (class "Default")
      (node (ref "LD6") (pin "1") (pinfunction "A_1") (pintype "passive"))
      (node (ref "R17") (pin "2") (pinfunction "2_2") (pintype "passive"))
    )
    (net (code "54") (name "Net-(U4-NR)") (class "Default")
      (node (ref "C8") (pin "1") (pinfunction "1_1") (pintype "passive"))
      (node (ref "U4") (pin "4") (pinfunction "NR_4") (pintype "passive"))
    )
    (net (code "55") (name "Net-(U8-DCOUPL)") (class "Default")
      (node (ref "C24") (pin "1") (pinfunction "1_1") (pintype "passive"))
      (node (ref "U8") (pin "23") (pinfunction "DCOUPL_23") (pintype "power_in"))
    )
    (net (code "56") (name "Net-(U8-DIO_8)") (class "Default")
      (node (ref "R87") (pin "2") (pinfunction "2_2") (pintype "passive"))
      (node (ref "U8") (pin "14") (pinfunction "DIO_8_14") (pintype "bidirectional"))
    )
    (net (code "57") (name "Net-(U8-DIO_9)") (class "Default")
      (node (ref "R86") (pin "2") (pinfunction "2_2") (pintype "passive"))
      (node (ref "U8") (pin "15") (pinfunction "DIO_9_15") (pintype "bidirectional"))
    )
    (net (code "58") (name "Net-(U8-DIO_10)") (class "Default")
      (node (ref "R161") (pin "2") (pinfunction "2_2") (pintype "passive"))
      (node (ref "U8") (pin "16") (pinfunction "DIO_10_16") (pintype "bidirectional"))
    )
    (net (code "59") (name "Net-(U8-DIO_19)") (class "Default")
      (node (ref "R131") (pin "2") (pinfunction "2_2") (pintype "passive"))
      (node (ref "U8") (pin "29") (pinfunction "DIO_19_29") (pintype "bidirectional"))
    )
    (net (code "60") (name "Net-(U10-P3)") (class "Default")
      (node (ref "R100") (pin "2") (pinfunction "2_2") (pintype "passive"))
      (node (ref "U10") (pin "5") (pinfunction "P3_5") (pintype "bidirectional"))
    )
    (net (code "61") (name "Net-(U10-P5)") (class "Default")
      (node (ref "R112") (pin "2") (pinfunction "2_2") (pintype "passive"))
      (node (ref "U10") (pin "8") (pinfunction "P5_8") (pintype "bidirectional"))
    )
    (net (code "62") (name "Net-(U10-P6)") (class "Default")
      (node (ref "R113") (pin "2") (pinfunction "2_2") (pintype "passive"))
      (node (ref "U10") (pin "9") (pinfunction "P6_9") (pintype "bidirectional"))
    )
    (net (code "63") (name "Net-(U10-P7)") (class "Default")
      (node (ref "R30") (pin "2") (pinfunction "2_2") (pintype "passive"))
      (node (ref "U10") (pin "10") (pinfunction "P7_10") (pintype "bidirectional"))
    )
    (net (code "64") (name "Net-(U10-SCL)") (class "Default")
      (node (ref "R99") (pin "1") (pinfunction "1_1") (pintype "passive"))
      (node (ref "U10") (pin "12") (pinfunction "SCL_12") (pintype "input"))
    )
    (net (code "65") (name "Net-(U10-SDA)") (class "Default")
      (node (ref "R101") (pin "1") (pinfunction "1_1") (pintype "passive"))
      (node (ref "U10") (pin "13") (pinfunction "SDA_13") (pintype "bidirectional"))
    )
    (net (code "66") (name "Net-(U14-B1)") (class "Default")
      (node (ref "R160") (pin "1") (pinfunction "1_1") (pintype "passive"))
      (node (ref "U14") (pin "10") (pinfunction "B1_10") (pintype "bidirectional"))
    )
    (net (code "67") (name "Net-(U14-B2)") (class "Default")
      (node (ref "R166") (pin "1") (pinfunction "1_1") (pintype "passive"))
      (node (ref "U14") (pin "9") (pinfunction "B2_9") (pintype "bidirectional"))
    )
    (net (code "68") (name "Net-(U14-B3)") (class "Default")
      (node (ref "R76") (pin "1") (pinfunction "1_1") (pintype "passive"))
      (node (ref "U14") (pin "8") (pinfunction "B3_8") (pintype "bidirectional"))
    )
    (net (code "69") (name "Net-(U14-B4)") (class "Default")
      (node (ref "R168") (pin "1") (pinfunction "1_1") (pintype "passive"))
      (node (ref "U14") (pin "7") (pinfunction "B4_7") (pintype "bidirectional"))
    )
    (net (code "70") (name "Net-(U14-OE)") (class "Default")
      (node (ref "R79") (pin "1") (pinfunction "1_1") (pintype "passive"))
      (node (ref "U14") (pin "12") (pinfunction "OE_12") (pintype "input"))
    )
    (net (code "71") (name "VCC_BA_3V3") (class "Default")
      (node (ref "C117") (pin "1") (pinfunction "1_1") (pintype "passive"))
      (node (ref "C119") (pin "1") (pinfunction "1_1") (pintype "passive"))
      (node (ref "C5") (pin "1") (pinfunction "1_1") (pintype "passive"))
      (node (ref "J7") (pin "1") (pinfunction "1_1") (pintype "passive"))
      (node (ref "L8") (pin "1") (pinfunction "1_1") (pintype "passive"))
      (node (ref "R89") (pin "2") (pinfunction "2_2") (pintype "passive"))
      (node (ref "R94") (pin "2") (pinfunction "2_2") (pintype "passive"))
      (node (ref "R95") (pin "2") (pinfunction "2_2") (pintype "passive"))
      (node (ref "U10") (pin "14") (pinfunction "VCCP_14") (pintype "power_in"))
      (node (ref "U10") (pin "15") (pinfunction "VCCI_15") (pintype "power_in"))
      (node (ref "U14") (pin "11") (pinfunction "VCCB_11") (pintype "power_in"))
      (node (ref "U4") (pin "1") (pinfunction "IN_1") (pintype "power_in"))
      (node (ref "U4") (pin "3") (pinfunction "EN_3") (pintype "input"))
    )
    (net (code "72") (name "VDDR") (class "Default")
      (node (ref "C29") (pin "1") (pinfunction "1_1") (pintype "passive"))
      (node (ref "C35") (pin "1") (pinfunction "1_1") (pintype "passive"))
      (node (ref "C36") (pin "1") (pinfunction "1_1") (pintype "passive"))
      (node (ref "L7") (pin "2") (pinfunction "2_2") (pintype "passive"))
      (node (ref "U8") (pin "45") (pinfunction "VDDR_45") (pintype "power_in"))
      (node (ref "U8") (pin "48") (pinfunction "VDDR_RF_48") (pintype "power_in"))
    )
    (net (code "73") (name "VDDS") (class "Default")
      (node (ref "C25") (pin "1") (pinfunction "1_1") (pintype "passive"))
      (node (ref "C26") (pin "1") (pinfunction "1_1") (pintype "passive"))
      (node (ref "C27") (pin "1") (pinfunction "1_1") (pintype "passive"))
      (node (ref "C28") (pin "1") (pinfunction "1_1") (pintype "passive"))
      (node (ref "C86") (pin "1") (pinfunction "1_1") (pintype "passive"))
      (node (ref "L8") (pin "2") (pinfunction "2_2") (pintype "passive"))
      (node (ref "R110") (pin "2") (pinfunction "2_2") (pintype "passive"))
      (node (ref "U8") (pin "13") (pinfunction "VDDS2_13") (pintype "power_in"))
      (node (ref "U8") (pin "22") (pinfunction "VDDS3_22") (pintype "power_in"))
      (node (ref "U8") (pin "34") (pinfunction "VDDS_DCDC_34") (pintype "power_in"))
      (node (ref "U8") (pin "44") (pinfunction "VDDS_44") (pintype "power_in"))
    )
    (net (code "74") (name "unconnected-(A1-NC-Pad2-3)") (class "Default")
      (node (ref "A1") (pin "2-3") (pinfunction "NC_2-3") (pintype "passive+no_connect"))
    )
    (net (code "75") (name "unconnected-(A1-NC-Pad5-6)") (class "Default")
      (node (ref "A1") (pin "5-6") (pinfunction "NC_5-6") (pintype "passive+no_connect"))
    )
    (net (code "76") (name "unconnected-(J4-Pad4)") (class "Default")
      (node (ref "J4") (pin "4") (pinfunction "4_4") (pintype "passive+no_connect"))
    )
    (net (code "77") (name "unconnected-(J6-Pad4)") (class "Default")
      (node (ref "J6") (pin "4") (pinfunction "4_4") (pintype "passive+no_connect"))
    )
    (net (code "78") (name "unconnected-(U8-DIO_0-Pad5)") (class "Default")
      (node (ref "U8") (pin "5") (pinfunction "DIO_0_5") (pintype "bidirectional+no_connect"))
    )
    (net (code "79") (name "unconnected-(U8-DIO_1-Pad6)") (class "Default")
      (node (ref "U8") (pin "6") (pinfunction "DIO_1_6") (pintype "bidirectional+no_connect"))
    )
    (net (code "80") (name "unconnected-(U8-DIO_4-Pad9)") (class "Default")
      (node (ref "U8") (pin "9") (pinfunction "DIO_4_9") (pintype "bidirectional+no_connect"))
    )
    (net (code "81") (name "unconnected-(U8-DIO_5-Pad10)") (class "Default")
      (node (ref "U8") (pin "10") (pinfunction "DIO_5_10") (pintype "bidirectional+no_connect"))
    )
    (net (code "82") (name "unconnected-(U8-DIO_7-Pad12)") (class "Default")
      (node (ref "U8") (pin "12") (pinfunction "DIO_7_12") (pintype "bidirectional+no_connect"))
    )
    (net (code "83") (name "unconnected-(U8-DIO_12-Pad18)") (class "Default")
      (node (ref "U8") (pin "18") (pinfunction "DIO_12_18") (pintype "bidirectional+no_connect"))
    )
    (net (code "84") (name "unconnected-(U8-DIO_13-Pad19)") (class "Default")
      (node (ref "U8") (pin "19") (pinfunction "DIO_13_19") (pintype "bidirectional+no_connect"))
    )
    (net (code "85") (name "unconnected-(U8-DIO_14-Pad20)") (class "Default")
      (node (ref "U8") (pin "20") (pinfunction "DIO_14_20") (pintype "bidirectional+no_connect"))
    )
    (net (code "86") (name "unconnected-(U8-DIO_18-Pad28)") (class "Default")
      (node (ref "U8") (pin "28") (pinfunction "DIO_18_28") (pintype "bidirectional+no_connect"))
    )
    (net (code "87") (name "unconnected-(U8-DIO_22-Pad32)") (class "Default")
      (node (ref "U8") (pin "32") (pinfunction "DIO_22_32") (pintype "bidirectional"))
    )
    (net (code "88") (name "unconnected-(U8-DIO_23-Pad36)") (class "Default")
      (node (ref "U8") (pin "36") (pinfunction "DIO_23_36") (pintype "bidirectional"))
    )
    (net (code "89") (name "unconnected-(U8-DIO_24-Pad37)") (class "Default")
      (node (ref "U8") (pin "37") (pinfunction "DIO_24_37") (pintype "bidirectional"))
    )
    (net (code "90") (name "unconnected-(U8-DIO_25-Pad38)") (class "Default")
      (node (ref "U8") (pin "38") (pinfunction "DIO_25_38") (pintype "bidirectional+no_connect"))
    )
    (net (code "91") (name "unconnected-(U8-DIO_26-Pad39)") (class "Default")
      (node (ref "U8") (pin "39") (pinfunction "DIO_26_39") (pintype "bidirectional+no_connect"))
    )
    (net (code "92") (name "unconnected-(U8-DIO_27-Pad40)") (class "Default")
      (node (ref "U8") (pin "40") (pinfunction "DIO_27_40") (pintype "bidirectional+no_connect"))
    )
    (net (code "93") (name "unconnected-(U8-DIO_28-Pad41)") (class "Default")
      (node (ref "U8") (pin "41") (pinfunction "DIO_28_41") (pintype "bidirectional+no_connect"))
    )
    (net (code "94") (name "unconnected-(U8-DIO_29-Pad42)") (class "Default")
      (node (ref "U8") (pin "42") (pinfunction "DIO_29_42") (pintype "bidirectional+no_connect"))
    )
    (net (code "95") (name "unconnected-(U8-DIO_30-Pad43)") (class "Default")
      (node (ref "U8") (pin "43") (pinfunction "DIO_30_43") (pintype "bidirectional+no_connect"))
    )
  )
)
